# Car_Power_Supply_2x_Line_v2_0.net
KiCad netlist of a schematic drawn in Altium Designer
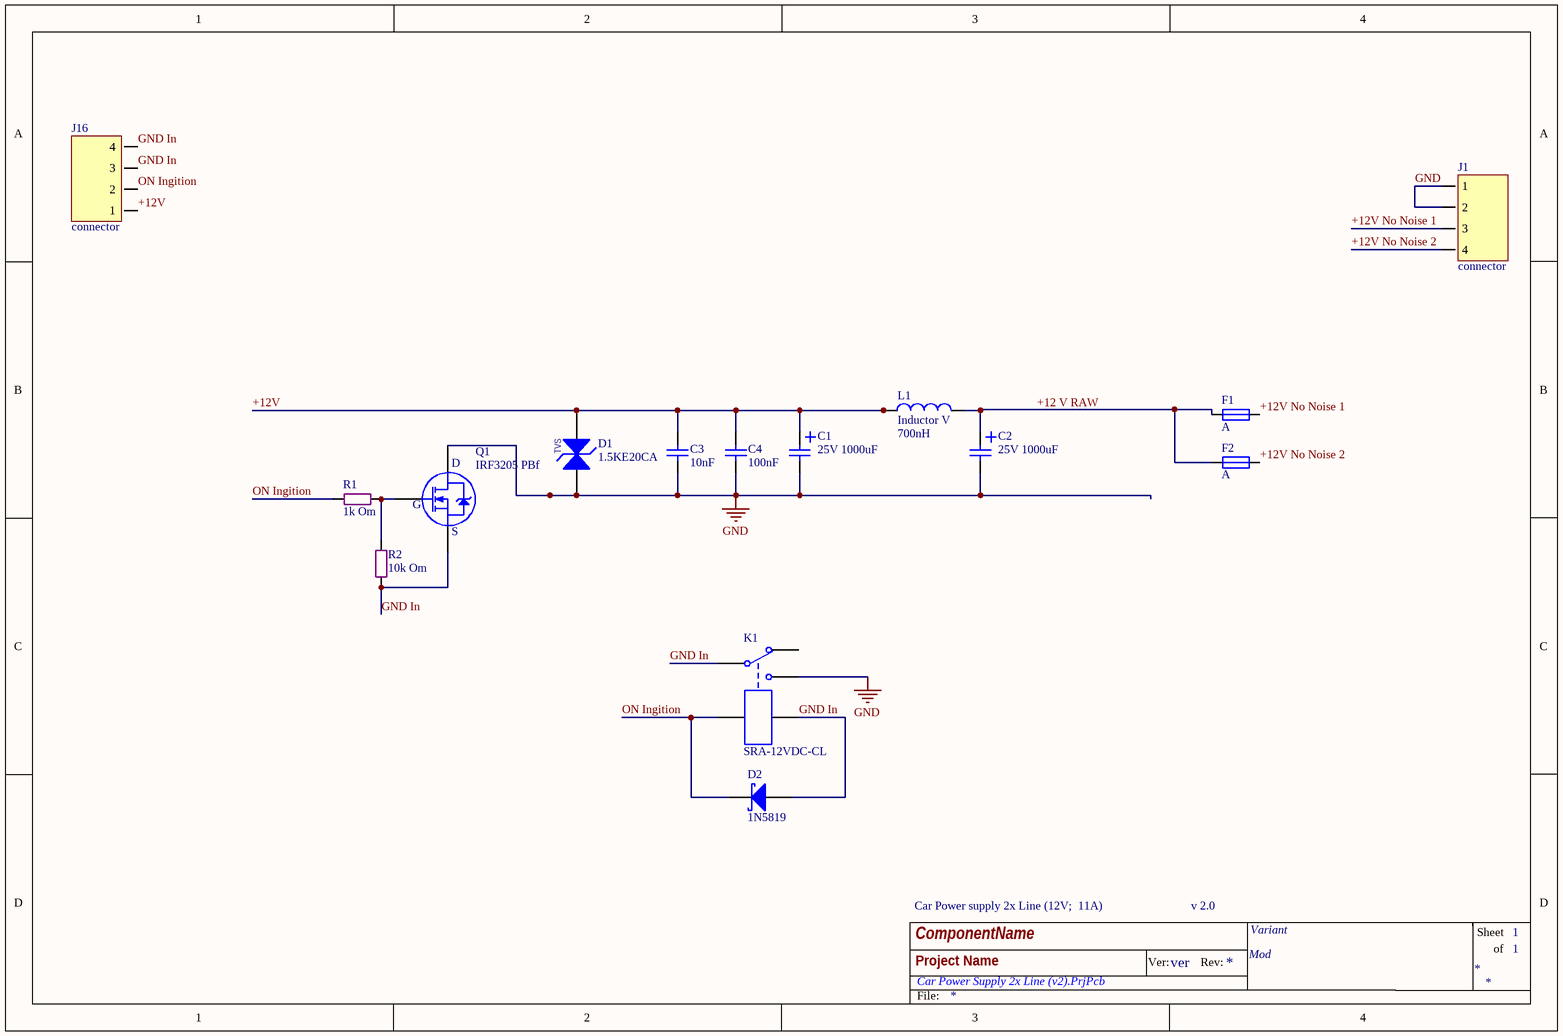
[diagram p0: Car Power Supply 2x Line v2.0.SchDoc]

(export (version "E")
  (design (tool "Eeschema 10.0.6"))
  (components
    (comp (ref "C1")
      (value "25V 1000uF")
      (footprint "Capacitor:Cap E p5.08mm D10.2mm (3p)")
      (description "Capacitor")
      (libsource (lib "Capacitor") (part "Cap E 1000mF x 25V"))
    )
    (comp (ref "C2")
      (value "25V 1000uF")
      (footprint "Capacitor:Cap E p5.08mm D10.2mm (3p)")
      (description "Capacitor")
      (libsource (lib "Capacitor") (part "Cap E 1000mF x 25V"))
    )
    (comp (ref "C3")
      (value "10nF")
      (footprint "Capacitor:SMD 1206 (3216)")
      (description "Capacitor")
      (libsource (lib "Capacitor") (part "Cap Ceramic SMD (All)"))
    )
    (comp (ref "C4")
      (value "100nF")
      (footprint "Capacitor:SMD 1206 (3216)")
      (description "Capacitor")
      (libsource (lib "Capacitor") (part "Cap Ceramic SMD (All)"))
    )
    (comp (ref "D1")
      (value "1.5KE20CA")
      (footprint "Diodes:TVS diode DO-201 V")
      (description "1500W Transil (TVS Diode)")
      (libsource (lib "Diodes") (part "TVS 1.5KE20CA"))
    )
    (comp (ref "D2")
      (value "1N5819")
      (footprint "Diodes:Diode DO-35")
      (description "Shotki  Diode")
      (libsource (lib "Diodes") (part "D Shotki All"))
    )
    (comp (ref "F1")
      (value "A")
      (footprint "PassiveComponents:Fuse RGE1100")
      (description "Round fuse")
      (libsource (lib "PassiveComponents") (part "Fuse"))
    )
    (comp (ref "F2")
      (value "A")
      (footprint "PassiveComponents:Fuse RGE1100")
      (description "Round fuse")
      (libsource (lib "PassiveComponents") (part "Fuse"))
    )
    (comp (ref "J1")
      (value "connector")
      (footprint "Connector:Molex Mini-Fit Jr - 4Pin V")
      (description "Right, Dbl line, Female")
      (libsource (lib "") (part "Molex Mini-Fit Jr - 4 pin_1"))
    )
    (comp (ref "J16")
      (value "connector")
      (footprint "Connector:Molex Mini-Fit Jr - 4Pin V")
      (description "Right, Dbl line, Female")
      (libsource (lib "Connector") (part "Molex Mini-Fit Jr - 4 pin"))
    )
    (comp (ref "K1")
      (value "SRA-12VDC-CL")
      (footprint "Relay:SRA-12VDC-CL")
      (description "Single-Pole Dual-Throw Relay")
      (libsource (lib "Relay") (part "SRA-12VDC-CL"))
    )
    (comp (ref "L1")
      (value "Inductor V")
      (footprint "Transformers:Toroid V D20 W7")
      (description "Inductor Vertical")
      (fields (field (name "ALTIUM_VALUE") "700nH") (field (name "PUBLISHER") "Altium Limited"))
      (libsource (lib "Transformers") (part "Inductor V"))
    )
    (comp (ref "Q1")
      (value "IRF3205 PBf")
      (footprint "GeneralCases:TO220-2 HighPower")
      (description "N-Channel 55V - 0.008Ω - 110A")
      (libsource (lib "Transistor") (part "IRF3205"))
    )
    (comp (ref "R1")
      (value "1k Om")
      (footprint "PassiveComponents:SMD 0805 (2012)")
      (libsource (lib "PassiveComponents") (part "Res All Types"))
    )
    (comp (ref "R2")
      (value "10k Om")
      (footprint "PassiveComponents:SMD 0805 (2012)")
      (libsource (lib "PassiveComponents") (part "Res All Types"))
    )
  )
  (nets
    (net (code "2") (name "/+12V") (class "Default")
      (node (ref "C1") (pin "1") (pinfunction "1_1") (pintype "passive"))
      (node (ref "C3") (pin "1") (pinfunction "1_1") (pintype "passive"))
      (node (ref "C4") (pin "1") (pinfunction "1_1") (pintype "passive"))
      (node (ref "D1") (pin "2") (pinfunction "2_2") (pintype "passive"))
      (node (ref "J16") (pin "1") (pinfunction "1_1") (pintype "passive"))
      (node (ref "L1") (pin "1") (pinfunction "1_1") (pintype "passive"))
    )
    (net (code "3") (name "/+12V No Noise 1") (class "Default")
      (node (ref "F1") (pin "2") (pinfunction "2_2") (pintype "passive"))
      (node (ref "J1") (pin "3") (pinfunction "3_3") (pintype "passive"))
    )
    (net (code "4") (name "/+12V No Noise 2") (class "Default")
      (node (ref "F2") (pin "2") (pinfunction "2_2") (pintype "passive"))
      (node (ref "J1") (pin "4") (pinfunction "4_4") (pintype "passive"))
    )
    (net (code "5") (name "/GND In") (class "Default")
      (node (ref "D2") (pin "A") (pinfunction "A_A") (pintype "passive"))
      (node (ref "J16") (pin "3") (pinfunction "3_3") (pintype "passive"))
      (node (ref "J16") (pin "4") (pinfunction "4_4") (pintype "passive"))
      (node (ref "K1") (pin "2") (pinfunction "2_2") (pintype "passive"))
      (node (ref "K1") (pin "5") (pinfunction "5_5") (pintype "passive"))
      (node (ref "Q1") (pin "3") (pinfunction "S_3") (pintype "passive"))
      (node (ref "R2") (pin "1") (pinfunction "1_1") (pintype "passive"))
    )
    (net (code "6") (name "/ON Ingition") (class "Default")
      (node (ref "D2") (pin "K") (pinfunction "K_K") (pintype "passive"))
      (node (ref "J16") (pin "2") (pinfunction "2_2") (pintype "passive"))
      (node (ref "K1") (pin "4") (pinfunction "4_4") (pintype "passive"))
      (node (ref "R1") (pin "1") (pinfunction "1_1") (pintype "passive"))
    )
    (net (code "7") (name "GND") (class "Default")
      (node (ref "C1") (pin "2") (pinfunction "2_2") (pintype "passive"))
      (node (ref "C2") (pin "2") (pinfunction "2_2") (pintype "passive"))
      (node (ref "C3") (pin "2") (pinfunction "2_2") (pintype "passive"))
      (node (ref "C4") (pin "2") (pinfunction "2_2") (pintype "passive"))
      (node (ref "D1") (pin "1") (pinfunction "1_1") (pintype "passive"))
      (node (ref "J1") (pin "1") (pinfunction "1_1") (pintype "passive"))
      (node (ref "J1") (pin "2") (pinfunction "2_2") (pintype "passive"))
      (node (ref "K1") (pin "3") (pinfunction "3_3") (pintype "passive"))
      (node (ref "Q1") (pin "2") (pinfunction "D_2") (pintype "passive"))
    )
    (net (code "8") (name "Net-(C2-Pad1)") (class "Default")
      (node (ref "C2") (pin "1") (pinfunction "1_1") (pintype "passive"))
      (node (ref "F1") (pin "1") (pinfunction "1_1") (pintype "passive"))
      (node (ref "F2") (pin "1") (pinfunction "1_1") (pintype "passive"))
      (node (ref "L1") (pin "2") (pinfunction "2_2") (pintype "passive"))
    )
    (net (code "9") (name "Net-(Q1-G)") (class "Default")
      (node (ref "Q1") (pin "1") (pinfunction "G_1") (pintype "passive"))
      (node (ref "R1") (pin "2") (pinfunction "2_2") (pintype "passive"))
      (node (ref "R2") (pin "2") (pinfunction "2_2") (pintype "passive"))
    )
    (net (code "10") (name "unconnected-(K1-Pad1)") (class "Default")
      (node (ref "K1") (pin "1") (pinfunction "1_1") (pintype "passive"))
    )
  )
)
